# reloadpro.net
KiCad netlist of a schematic drawn in EAGLE
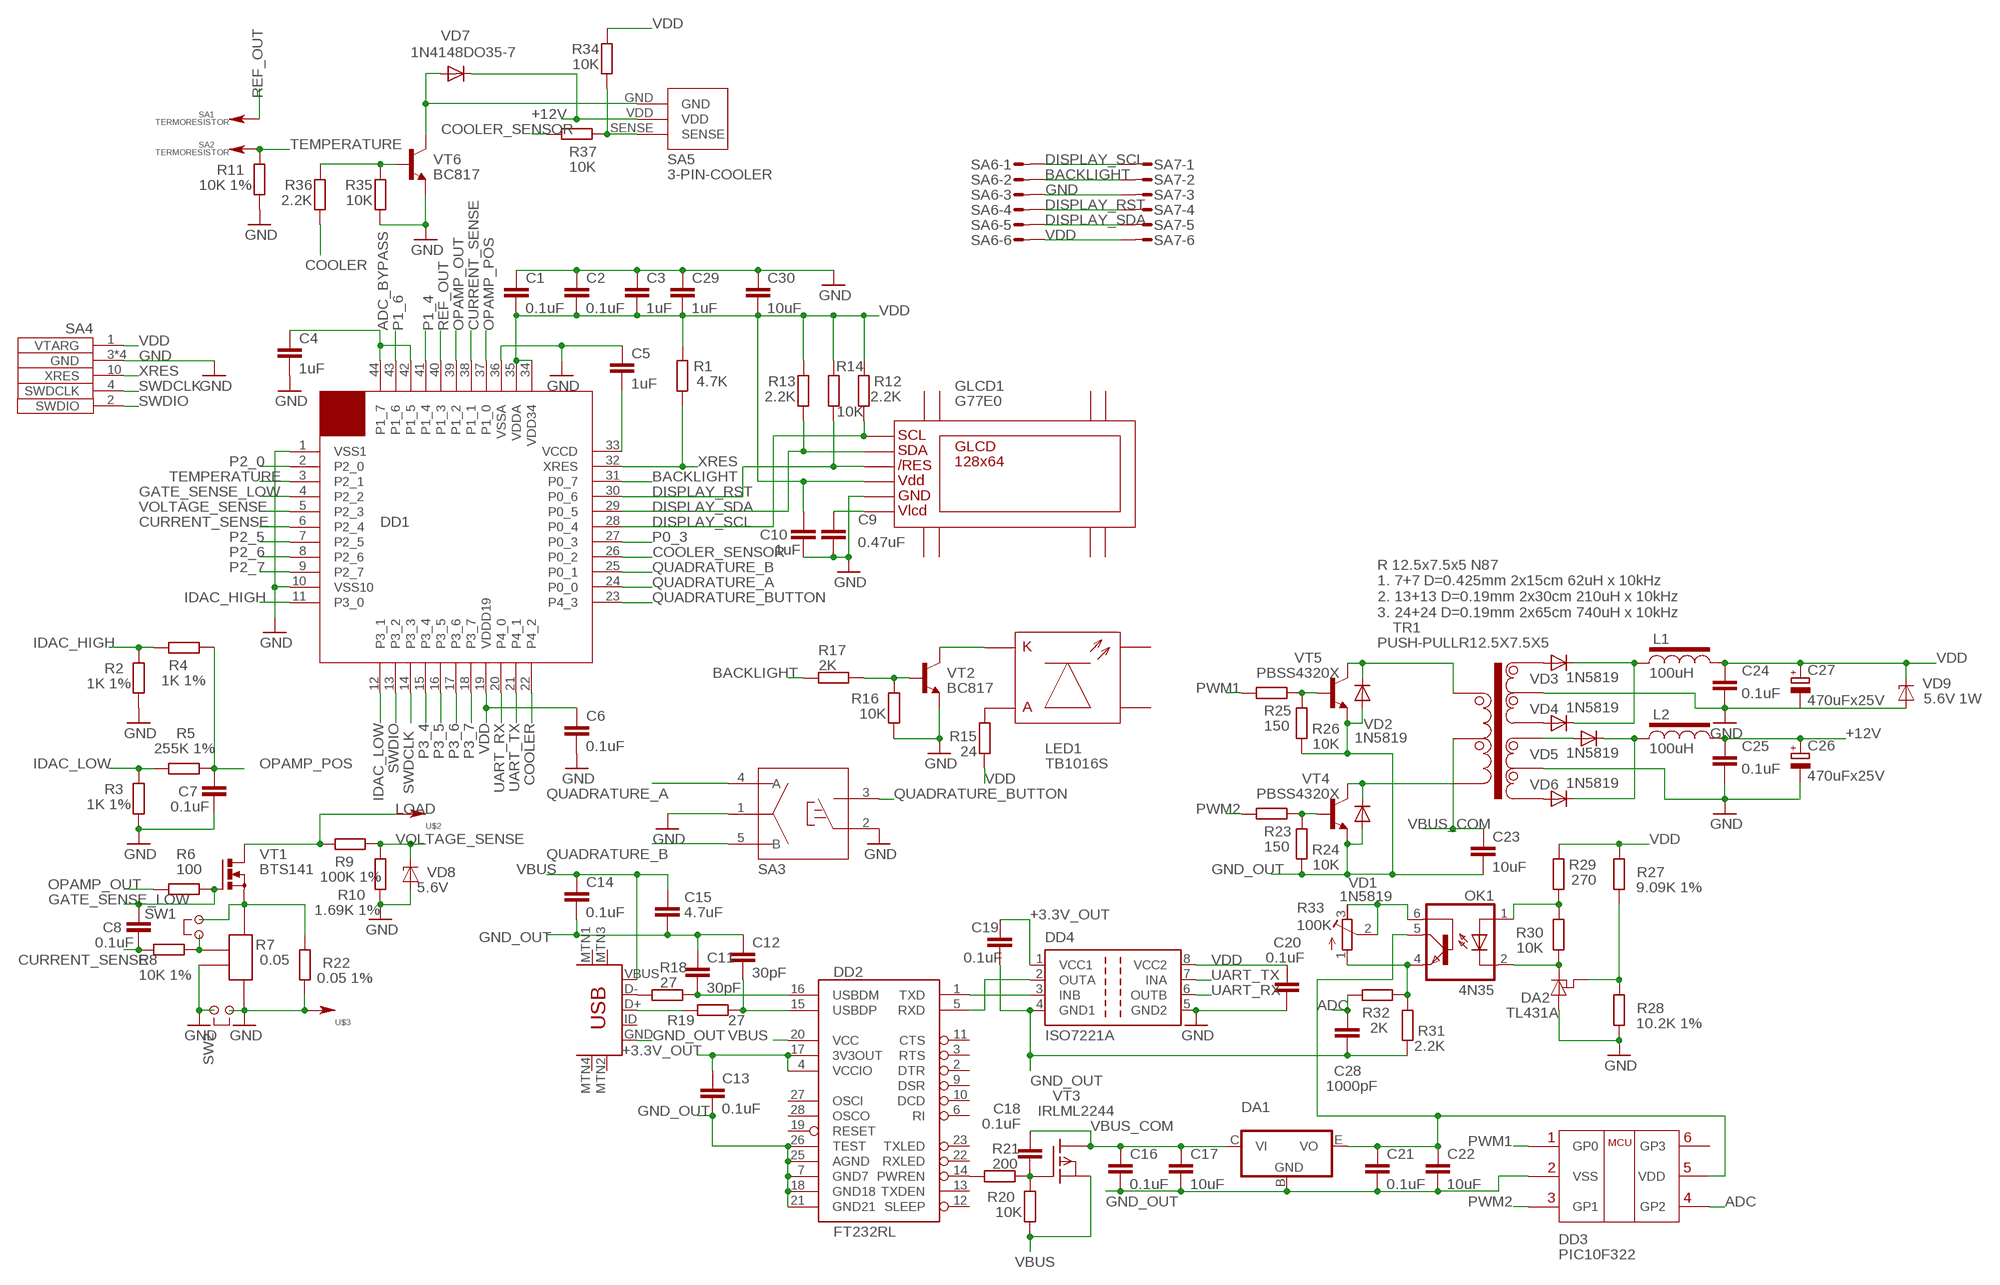
[diagram p0: schematic, sheet 1]

(export (version "E")
  (design (tool "Eeschema 10.0.6"))
  (components
    (comp (ref "C1")
      (value "0.1uF")
      (footprint "eagle-import:C0603")
      (libsource (lib "eagle-import") (part "C-EUC0603"))
    )
    (comp (ref "C2")
      (value "0.1uF")
      (footprint "eagle-import:C0603")
      (libsource (lib "eagle-import") (part "C-EUC0603"))
    )
    (comp (ref "C3")
      (value "1uF")
      (footprint "eagle-import:C0603")
      (libsource (lib "eagle-import") (part "C-EUC0603"))
    )
    (comp (ref "C4")
      (value "1uF")
      (footprint "eagle-import:C0603")
      (libsource (lib "eagle-import") (part "C-EUC0603"))
    )
    (comp (ref "C5")
      (value "1uF")
      (footprint "eagle-import:C0603")
      (libsource (lib "eagle-import") (part "C-EUC0603"))
    )
    (comp (ref "C6")
      (value "0.1uF")
      (footprint "eagle-import:C0603")
      (libsource (lib "eagle-import") (part "C-EUC0603"))
    )
    (comp (ref "C7")
      (value "0.1uF")
      (footprint "eagle-import:C0603")
      (libsource (lib "eagle-import") (part "C-EUC0603"))
    )
    (comp (ref "C8")
      (value "0.1uF")
      (footprint "eagle-import:C0603")
      (libsource (lib "eagle-import") (part "C-EUC0603"))
    )
    (comp (ref "C9")
      (value "0.47uF")
      (footprint "eagle-import:C1206")
      (libsource (lib "eagle-import") (part "C-EUC1206"))
    )
    (comp (ref "C10")
      (value "1uF")
      (footprint "eagle-import:C0603")
      (libsource (lib "eagle-import") (part "C-EUC0603"))
    )
    (comp (ref "C11")
      (value "30pF")
      (footprint "eagle-import:C0603")
      (libsource (lib "eagle-import") (part "C-EUC0603"))
    )
    (comp (ref "C12")
      (value "30pF")
      (footprint "eagle-import:C0603")
      (libsource (lib "eagle-import") (part "C-EUC0603"))
    )
    (comp (ref "C13")
      (value "0.1uF")
      (footprint "eagle-import:C0603")
      (libsource (lib "eagle-import") (part "C-EUC0603"))
    )
    (comp (ref "C14")
      (value "0.1uF")
      (footprint "eagle-import:C0603")
      (libsource (lib "eagle-import") (part "C-EUC0603"))
    )
    (comp (ref "C15")
      (value "4.7uF")
      (footprint "eagle-import:C0805")
      (libsource (lib "eagle-import") (part "C-EUC0805"))
    )
    (comp (ref "C16")
      (value "0.1uF")
      (footprint "eagle-import:C0603")
      (libsource (lib "eagle-import") (part "C-EUC0603"))
    )
    (comp (ref "C17")
      (value "10uF")
      (footprint "eagle-import:C1206")
      (libsource (lib "eagle-import") (part "C-EUC1206"))
    )
    (comp (ref "C18")
      (value "0.1uF")
      (footprint "eagle-import:C0603")
      (libsource (lib "eagle-import") (part "C-EUC0603"))
    )
    (comp (ref "C19")
      (value "0.1uF")
      (footprint "eagle-import:C0603")
      (libsource (lib "eagle-import") (part "C-EUC0603"))
    )
    (comp (ref "C20")
      (value "0.1uF")
      (footprint "eagle-import:C0603")
      (libsource (lib "eagle-import") (part "C-EUC0603"))
    )
    (comp (ref "C21")
      (value "0.1uF")
      (footprint "eagle-import:C0603")
      (libsource (lib "eagle-import") (part "C-EUC0603"))
    )
    (comp (ref "C22")
      (value "10uF")
      (footprint "eagle-import:C1206")
      (libsource (lib "eagle-import") (part "C-EUC1206"))
    )
    (comp (ref "C23")
      (value "10uF")
      (footprint "eagle-import:C1206")
      (libsource (lib "eagle-import") (part "C-EUC1206"))
    )
    (comp (ref "C24")
      (value "0.1uF")
      (footprint "eagle-import:C0603")
      (libsource (lib "eagle-import") (part "C-EUC0603"))
    )
    (comp (ref "C25")
      (value "0.1uF")
      (footprint "eagle-import:C0805")
      (libsource (lib "eagle-import") (part "C-EUC0805"))
    )
    (comp (ref "C26")
      (value "470uFx25V")
      (footprint "eagle-import:E3,5-8")
      (libsource (lib "eagle-import") (part "CPOL-EUE3.5-8"))
    )
    (comp (ref "C27")
      (value "470uFx25V")
      (footprint "eagle-import:E3,5-8")
      (libsource (lib "eagle-import") (part "CPOL-EUE3.5-8"))
    )
    (comp (ref "C28")
      (value "1000pF")
      (footprint "eagle-import:C0805")
      (libsource (lib "eagle-import") (part "C-EUC0805"))
    )
    (comp (ref "C29")
      (value "1uF")
      (footprint "eagle-import:C0603")
      (libsource (lib "eagle-import") (part "C-EUC0603"))
    )
    (comp (ref "C30")
      (value "10uF")
      (footprint "eagle-import:C0805")
      (libsource (lib "eagle-import") (part "C-EUC0805"))
    )
    (comp (ref "DA1")
      (value "78GOR")
      (footprint "eagle-import:TO92-EBC")
      (libsource (lib "eagle-import") (part "78GOR"))
    )
    (comp (ref "DA2")
      (value "TL431A")
      (footprint "eagle-import:TO92-EBC")
      (libsource (lib "eagle-import") (part "TL431TO92"))
    )
    (comp (ref "DD1")
      (value "CY8C4245-AXITQFP44")
      (footprint "eagle-import:TQFP44")
      (libsource (lib "eagle-import") (part "CY8C4245-AXITQFP44"))
    )
    (comp (ref "DD2")
      (value "FT232RL")
      (footprint "eagle-import:SSOP28DB")
      (libsource (lib "eagle-import") (part "FT232RLSSOP"))
    )
    (comp (ref "DD3")
      (value "PIC10F322")
      (footprint "eagle-import:SOT23-6")
      (libsource (lib "eagle-import") (part "PIC10F20XSOT23-6"))
    )
    (comp (ref "DD4")
      (value "ISO7221A")
      (footprint "eagle-import:SO-08")
      (fields (field (name "MPN") "ISO7221AD"))
      (libsource (lib "eagle-import") (part "ISO7221A"))
    )
    (comp (ref "GLCD1")
      (value "G77E0")
      (footprint "eagle-import:G77E0")
      (libsource (lib "eagle-import") (part "G77E0"))
    )
    (comp (ref "L1")
      (value "100uH")
      (footprint "eagle-import:LGA0410")
      (libsource (lib "eagle-import") (part "INDUCTORLGA0410_HOME"))
    )
    (comp (ref "L2")
      (value "100uH")
      (footprint "eagle-import:LGA0410")
      (libsource (lib "eagle-import") (part "INDUCTORLGA0410_HOME"))
    )
    (comp (ref "LED1")
      (value "TB1016S")
      (footprint "eagle-import:TB1016S")
      (libsource (lib "eagle-import") (part "TB1016S"))
    )
    (comp (ref "OK1")
      (value "4N35")
      (footprint "eagle-import:DIL06")
      (fields (field (name "MF") "FAIRCHILD SEMICONDUCTOR"))
      (libsource (lib "eagle-import") (part "4N35"))
    )
    (comp (ref "R1")
      (value "4.7K")
      (footprint "eagle-import:R0603")
      (libsource (lib "eagle-import") (part "R-EU_R0603"))
    )
    (comp (ref "R2")
      (value "1K 1%")
      (footprint "eagle-import:R0603")
      (libsource (lib "eagle-import") (part "R-EU_R0603"))
    )
    (comp (ref "R3")
      (value "1K 1%")
      (footprint "eagle-import:R0603")
      (libsource (lib "eagle-import") (part "R-EU_R0603"))
    )
    (comp (ref "R4")
      (value "1K 1%")
      (footprint "eagle-import:R0603")
      (libsource (lib "eagle-import") (part "R-EU_R0603"))
    )
    (comp (ref "R5")
      (value "255K 1%")
      (footprint "eagle-import:R0805")
      (libsource (lib "eagle-import") (part "R-EU_R0805"))
    )
    (comp (ref "R6")
      (value "100")
      (footprint "eagle-import:R0805")
      (libsource (lib "eagle-import") (part "R-EU_R0805"))
    )
    (comp (ref "R7")
      (value "0.05")
      (footprint "eagle-import:SR10")
      (libsource (lib "eagle-import") (part "SR10SR10"))
    )
    (comp (ref "R8")
      (value "10K 1%")
      (footprint "eagle-import:R0603")
      (libsource (lib "eagle-import") (part "R-EU_R0603"))
    )
    (comp (ref "R9")
      (value "100K 1%")
      (footprint "eagle-import:R0603")
      (libsource (lib "eagle-import") (part "R-EU_R0603"))
    )
    (comp (ref "R10")
      (value "1.69K 1%")
      (footprint "eagle-import:R0805")
      (libsource (lib "eagle-import") (part "R-EU_R0805"))
    )
    (comp (ref "R11")
      (value "10K 1%")
      (footprint "eagle-import:R0603")
      (libsource (lib "eagle-import") (part "R-EU_R0603"))
    )
    (comp (ref "R12")
      (value "2.2K")
      (footprint "eagle-import:R0603")
      (libsource (lib "eagle-import") (part "R-EU_R0603"))
    )
    (comp (ref "R13")
      (value "2.2K")
      (footprint "eagle-import:R0603")
      (libsource (lib "eagle-import") (part "R-EU_R0603"))
    )
    (comp (ref "R14")
      (value "10K")
      (footprint "eagle-import:R0603")
      (libsource (lib "eagle-import") (part "R-EU_R0603"))
    )
    (comp (ref "R15")
      (value "24")
      (footprint "eagle-import:R1206")
      (libsource (lib "eagle-import") (part "R-EU_R1206"))
    )
    (comp (ref "R16")
      (value "10K")
      (footprint "eagle-import:R0603")
      (libsource (lib "eagle-import") (part "R-EU_R0603"))
    )
    (comp (ref "R17")
      (value "2K")
      (footprint "eagle-import:R0603")
      (libsource (lib "eagle-import") (part "R-EU_R0603"))
    )
    (comp (ref "R18")
      (value "27")
      (footprint "eagle-import:R0805")
      (libsource (lib "eagle-import") (part "R-EU_R0805"))
    )
    (comp (ref "R19")
      (value "27")
      (footprint "eagle-import:R0805")
      (libsource (lib "eagle-import") (part "R-EU_R0805"))
    )
    (comp (ref "R20")
      (value "10K")
      (footprint "eagle-import:R0603")
      (libsource (lib "eagle-import") (part "R-EU_R0603"))
    )
    (comp (ref "R21")
      (value "200")
      (footprint "eagle-import:R0603")
      (libsource (lib "eagle-import") (part "R-EU_R0603"))
    )
    (comp (ref "R22")
      (value "0.05 1%")
      (footprint "eagle-import:R2512")
      (libsource (lib "eagle-import") (part "R-EU_R2512"))
    )
    (comp (ref "R23")
      (value "150")
      (footprint "eagle-import:R0805")
      (libsource (lib "eagle-import") (part "R-EU_R0805"))
    )
    (comp (ref "R24")
      (value "10K")
      (footprint "eagle-import:R0603")
      (libsource (lib "eagle-import") (part "R-EU_R0603"))
    )
    (comp (ref "R25")
      (value "150")
      (footprint "eagle-import:R0805")
      (libsource (lib "eagle-import") (part "R-EU_R0805"))
    )
    (comp (ref "R26")
      (value "10K")
      (footprint "eagle-import:R0603")
      (libsource (lib "eagle-import") (part "R-EU_R0603"))
    )
    (comp (ref "R27")
      (value "9.09K 1%")
      (footprint "eagle-import:R0805")
      (libsource (lib "eagle-import") (part "R-EU_R0805"))
    )
    (comp (ref "R28")
      (value "10.2K 1%")
      (footprint "eagle-import:R0805")
      (libsource (lib "eagle-import") (part "R-EU_R0805"))
    )
    (comp (ref "R29")
      (value "270")
      (footprint "eagle-import:R0805")
      (libsource (lib "eagle-import") (part "R-EU_R0805"))
    )
    (comp (ref "R30")
      (value "10K")
      (footprint "eagle-import:R0603")
      (libsource (lib "eagle-import") (part "R-EU_R0603"))
    )
    (comp (ref "R31")
      (value "2.2K")
      (footprint "eagle-import:R0603")
      (libsource (lib "eagle-import") (part "R-EU_R0603"))
    )
    (comp (ref "R32")
      (value "2K")
      (footprint "eagle-import:R0603")
      (libsource (lib "eagle-import") (part "R-EU_R0603"))
    )
    (comp (ref "R33")
      (value "100K")
      (footprint "eagle-import:RTRIM3296H")
      (libsource (lib "eagle-import") (part "R-TRIMM3296H"))
    )
    (comp (ref "R34")
      (value "10K")
      (footprint "eagle-import:R0603")
      (libsource (lib "eagle-import") (part "R-EU_R0603"))
    )
    (comp (ref "R35")
      (value "10K")
      (footprint "eagle-import:R0603")
      (libsource (lib "eagle-import") (part "R-EU_R0603"))
    )
    (comp (ref "R36")
      (value "2.2K")
      (footprint "eagle-import:R0603")
      (libsource (lib "eagle-import") (part "R-EU_R0603"))
    )
    (comp (ref "R37")
      (value "10K")
      (footprint "eagle-import:R0603")
      (libsource (lib "eagle-import") (part "R-EU_R0603"))
    )
    (comp (ref "SA1")
      (value "TERMORESISTOR")
      (footprint "eagle-import:1-PIN_HOME")
      (libsource (lib "eagle-import") (part "1-PINHOME"))
    )
    (comp (ref "SA2")
      (value "TERMORESISTOR")
      (footprint "eagle-import:1-PIN_HOME")
      (libsource (lib "eagle-import") (part "1-PINHOME"))
    )
    (comp (ref "SA3")
      (value "PEC16IDC")
      (footprint "eagle-import:PEC16-IDC")
      (libsource (lib "eagle-import") (part "PEC16IDC"))
    )
    (comp (ref "SA4")
      (value "SWDSMD")
      (footprint "eagle-import:IDC10_1.27SMD")
      (libsource (lib "eagle-import") (part "SWDSMD"))
    )
    (comp (ref "SA5")
      (value "3-PIN-COOLER")
      (footprint "eagle-import:3-PIN-COOLER")
      (libsource (lib "eagle-import") (part "3-PIN-COOLER"))
    )
    (comp (ref "SA6")
      (value "MICROMATCH-6SMD")
      (footprint "eagle-import:MICROMATCH-6SMD")
      (libsource (lib "eagle-import") (part "MICROMATCH-6SMD"))
    )
    (comp (ref "SA7")
      (value "MICROMATCH-6SMD")
      (footprint "eagle-import:MICROMATCH-6SMD")
      (libsource (lib "eagle-import") (part "MICROMATCH-6SMD"))
    )
    (comp (ref "SW1")
      (value "2-PINDIL")
      (footprint "eagle-import:2-PIN")
      (libsource (lib "eagle-import") (part "2-PINDIL"))
    )
    (comp (ref "SW2")
      (value "2-PINDIL")
      (footprint "eagle-import:2-PIN")
      (libsource (lib "eagle-import") (part "2-PINDIL"))
    )
    (comp (ref "TR1")
      (value "PUSH-PULLR12.5X7.5X5")
      (footprint "eagle-import:R12.5X7.5X5PUSHH-PULL")
      (libsource (lib "eagle-import") (part "PUSH-PULLR12.5X7.5X5"))
    )
    (comp (ref "U$1")
      (value "USB-MINIB-5PIN")
      (footprint "eagle-import:USB-MINIB")
      (libsource (lib "eagle-import") (part "USB-MINIB-5PIN"))
    )
    (comp (ref "U$2")
      (value "1-PIN2_54")
      (footprint "eagle-import:1_PIN_2_54")
      (libsource (lib "eagle-import") (part "1-PIN2_54"))
    )
    (comp (ref "U$3")
      (value "1-PIN2_54")
      (footprint "eagle-import:1_PIN_2_54")
      (libsource (lib "eagle-import") (part "1-PIN2_54"))
    )
    (comp (ref "VD1")
      (value "1N5819")
      (footprint "eagle-import:DO41-10")
      (libsource (lib "eagle-import") (part "SM5819DO41-10"))
    )
    (comp (ref "VD2")
      (value "1N5819")
      (footprint "eagle-import:DO41-10")
      (libsource (lib "eagle-import") (part "SM5819DO41-10"))
    )
    (comp (ref "VD3")
      (value "1N5819")
      (footprint "eagle-import:DO41-10")
      (libsource (lib "eagle-import") (part "SM5819DO41-10"))
    )
    (comp (ref "VD4")
      (value "1N5819")
      (footprint "eagle-import:DO41-10")
      (libsource (lib "eagle-import") (part "SM5819DO41-10"))
    )
    (comp (ref "VD5")
      (value "1N5819")
      (footprint "eagle-import:DO41-10")
      (libsource (lib "eagle-import") (part "SM5819DO41-10"))
    )
    (comp (ref "VD6")
      (value "1N5819")
      (footprint "eagle-import:DO41-10")
      (libsource (lib "eagle-import") (part "SM5819DO41-10"))
    )
    (comp (ref "VD7")
      (value "1N4148DO35-7")
      (footprint "eagle-import:DO35-7")
      (libsource (lib "eagle-import") (part "1N4148DO35-7"))
    )
    (comp (ref "VD8")
      (value "5.6V")
      (footprint "eagle-import:STABILITRON")
      (libsource (lib "eagle-import") (part "STABILITRONSMD"))
    )
    (comp (ref "VD9")
      (value "5.6V 1W")
      (footprint "eagle-import:DO35-10")
      (libsource (lib "eagle-import") (part "STABILITRONDO35-10"))
    )
    (comp (ref "VT1")
      (value "BTS141")
      (footprint "eagle-import:TO220BV")
      (libsource (lib "eagle-import") (part "BTS141"))
    )
    (comp (ref "VT2")
      (value "BC817")
      (footprint "eagle-import:SOT23-BEC")
      (libsource (lib "eagle-import") (part "-NPN-SOT23-BECBC817-16LT1"))
    )
    (comp (ref "VT3")
      (value "IRLML2244")
      (footprint "eagle-import:SOT23")
      (libsource (lib "eagle-import") (part "P-MOSFETSOT23"))
    )
    (comp (ref "VT4")
      (value "PBSS4320X")
      (footprint "eagle-import:SOT89-BCE")
      (libsource (lib "eagle-import") (part "-NPN-SOT89-BCE"))
    )
    (comp (ref "VT5")
      (value "PBSS4320X")
      (footprint "eagle-import:SOT89-BCE")
      (libsource (lib "eagle-import") (part "-NPN-SOT89-BCE"))
    )
    (comp (ref "VT6")
      (value "BC817")
      (footprint "eagle-import:SOT23-BEC")
      (libsource (lib "eagle-import") (part "-NPN-SOT23-BECBC817-16LT1"))
    )
  )
  (nets
    (net (code "1") (name "/+3.3V_OUT") (class "Default")
      (node (ref "C13") (pin "1") (pinfunction "1_1") (pintype "passive"))
      (node (ref "C19") (pin "1") (pinfunction "1_1") (pintype "passive"))
      (node (ref "DD2") (pin "17") (pinfunction "3V3OUT_17") (pintype "output"))
      (node (ref "DD2") (pin "4") (pinfunction "VCCIO_4") (pintype "power_in"))
      (node (ref "DD4") (pin "1") (pinfunction "VCC1_1") (pintype "power_in"))
    )
    (net (code "2") (name "/+12V") (class "Default")
      (node (ref "C25") (pin "1") (pinfunction "1_1") (pintype "passive"))
      (node (ref "C26") (pin "+") (pinfunction "+_+") (pintype "passive"))
      (node (ref "L2") (pin "P$2") (pinfunction "L2_P$2") (pintype "passive"))
      (node (ref "SA5") (pin "VDD") (pinfunction "VDD_VDD") (pintype "power_in"))
      (node (ref "VD7") (pin "C") (pinfunction "C_C") (pintype "passive"))
    )
    (net (code "3") (name "/ADC") (class "Default")
      (node (ref "C28") (pin "1") (pinfunction "1_1") (pintype "passive"))
      (node (ref "DD3") (pin "4") (pinfunction "GP2_4") (pintype "bidirectional"))
      (node (ref "R32") (pin "1") (pinfunction "1_1") (pintype "passive"))
    )
    (net (code "4") (name "/ADC_BYPASS") (class "Default")
      (node (ref "C4") (pin "1") (pinfunction "1_1") (pintype "passive"))
      (node (ref "DD1") (pin "42") (pinfunction "P1_5_42") (pintype "bidirectional"))
      (node (ref "DD1") (pin "44") (pinfunction "P1_7_44") (pintype "bidirectional"))
    )
    (net (code "5") (name "/BACKLIGHT") (class "Default")
      (node (ref "DD1") (pin "31") (pinfunction "P0_7_31") (pintype "bidirectional"))
      (node (ref "R17") (pin "2") (pinfunction "2_2") (pintype "passive"))
      (node (ref "SA6") (pin "2") (pinfunction "S_2") (pintype "passive"))
      (node (ref "SA7") (pin "2") (pinfunction "S_2") (pintype "passive"))
    )
    (net (code "6") (name "/COOLER") (class "Default")
      (node (ref "DD1") (pin "22") (pinfunction "P4_2_22") (pintype "bidirectional"))
      (node (ref "R36") (pin "1") (pinfunction "1_1") (pintype "passive"))
    )
    (net (code "7") (name "/COOLER_SENSOR") (class "Default")
      (node (ref "DD1") (pin "26") (pinfunction "P0_2_26") (pintype "bidirectional"))
      (node (ref "R37") (pin "2") (pinfunction "2_2") (pintype "passive"))
    )
    (net (code "8") (name "/CURRENT_SENSE") (class "Default")
      (node (ref "C8") (pin "2") (pinfunction "2_2") (pintype "passive"))
      (node (ref "DD1") (pin "38") (pinfunction "P1_1_38") (pintype "bidirectional"))
      (node (ref "DD1") (pin "6") (pinfunction "P2_4_6") (pintype "bidirectional"))
      (node (ref "R8") (pin "2") (pinfunction "2_2") (pintype "passive"))
    )
    (net (code "9") (name "/DISPLAY_RST") (class "Default")
      (node (ref "DD1") (pin "30") (pinfunction "P0_6_30") (pintype "bidirectional"))
      (node (ref "GLCD1") (pin "/RES") (pinfunction "/RES_/RES") (pintype "input"))
      (node (ref "R14") (pin "1") (pinfunction "1_1") (pintype "passive"))
      (node (ref "SA6") (pin "4") (pinfunction "S_4") (pintype "passive"))
      (node (ref "SA7") (pin "4") (pinfunction "S_4") (pintype "passive"))
    )
    (net (code "10") (name "/DISPLAY_SCL") (class "Default")
      (node (ref "DD1") (pin "28") (pinfunction "P0_4_28") (pintype "bidirectional"))
      (node (ref "GLCD1") (pin "SCL") (pinfunction "SCL_SCL") (pintype "input"))
      (node (ref "R12") (pin "1") (pinfunction "1_1") (pintype "passive"))
      (node (ref "SA6") (pin "1") (pinfunction "S_1") (pintype "passive"))
      (node (ref "SA7") (pin "1") (pinfunction "S_1") (pintype "passive"))
    )
    (net (code "11") (name "/DISPLAY_SDA") (class "Default")
      (node (ref "DD1") (pin "29") (pinfunction "P0_5_29") (pintype "bidirectional"))
      (node (ref "GLCD1") (pin "SDA") (pinfunction "SDA_SDA") (pintype "bidirectional"))
      (node (ref "R13") (pin "1") (pinfunction "1_1") (pintype "passive"))
      (node (ref "SA6") (pin "5") (pinfunction "S_5") (pintype "passive"))
      (node (ref "SA7") (pin "5") (pinfunction "S_5") (pintype "passive"))
    )
    (net (code "12") (name "/GATE_SENSE_LOW") (class "Default")
      (node (ref "C8") (pin "1") (pinfunction "1_1") (pintype "passive"))
      (node (ref "DD1") (pin "4") (pinfunction "P2_2_4") (pintype "bidirectional"))
      (node (ref "R6") (pin "1") (pinfunction "1_1") (pintype "passive"))
      (node (ref "VT1") (pin "G") (pinfunction "G_G") (pintype "passive"))
    )
    (net (code "13") (name "/GND_OUT") (class "Default")
      (node (ref "C11") (pin "1") (pinfunction "1_1") (pintype "passive"))
      (node (ref "C12") (pin "1") (pinfunction "1_1") (pintype "passive"))
      (node (ref "C13") (pin "2") (pinfunction "2_2") (pintype "passive"))
      (node (ref "C14") (pin "2") (pinfunction "2_2") (pintype "passive"))
      (node (ref "C15") (pin "2") (pinfunction "2_2") (pintype "passive"))
      (node (ref "C16") (pin "2") (pinfunction "2_2") (pintype "passive"))
      (node (ref "C17") (pin "2") (pinfunction "2_2") (pintype "passive"))
      (node (ref "C19") (pin "2") (pinfunction "2_2") (pintype "passive"))
      (node (ref "C21") (pin "2") (pinfunction "2_2") (pintype "passive"))
      (node (ref "C22") (pin "2") (pinfunction "2_2") (pintype "passive"))
      (node (ref "C23") (pin "2") (pinfunction "2_2") (pintype "passive"))
      (node (ref "C28") (pin "2") (pinfunction "2_2") (pintype "passive"))
      (node (ref "DA1") (pin "B") (pinfunction "GND_B") (pintype "passive"))
      (node (ref "DD2") (pin "18") (pinfunction "GND18_18") (pintype "power_in"))
      (node (ref "DD2") (pin "21") (pinfunction "GND21_21") (pintype "power_in"))
      (node (ref "DD2") (pin "25") (pinfunction "AGND_25") (pintype "power_in"))
      (node (ref "DD2") (pin "26") (pinfunction "TEST_26") (pintype "input"))
      (node (ref "DD2") (pin "7") (pinfunction "GND7_7") (pintype "power_in"))
      (node (ref "DD3") (pin "2") (pinfunction "VSS_2") (pintype "power_in"))
      (node (ref "DD4") (pin "4") (pinfunction "GND1_4") (pintype "power_in"))
      (node (ref "R24") (pin "1") (pinfunction "1_1") (pintype "passive"))
      (node (ref "R26") (pin "1") (pinfunction "1_1") (pintype "passive"))
      (node (ref "R31") (pin "2") (pinfunction "2_2") (pintype "passive"))
      (node (ref "U$1") (pin "GND") (pinfunction "GND_GND") (pintype "bidirectional"))
      (node (ref "VD1") (pin "A") (pinfunction "A_A") (pintype "passive"))
      (node (ref "VD2") (pin "A") (pinfunction "A_A") (pintype "passive"))
      (node (ref "VT4") (pin "E") (pinfunction "E_E") (pintype "passive"))
      (node (ref "VT5") (pin "E") (pinfunction "E_E") (pintype "passive"))
    )
    (net (code "14") (name "/IDAC_HIGH") (class "Default")
      (node (ref "DD1") (pin "11") (pinfunction "P3_0_11") (pintype "bidirectional"))
      (node (ref "R2") (pin "2") (pinfunction "2_2") (pintype "passive"))
      (node (ref "R4") (pin "2") (pinfunction "2_2") (pintype "passive"))
    )
    (net (code "15") (name "/IDAC_LOW") (class "Default")
      (node (ref "DD1") (pin "12") (pinfunction "P3_1_12") (pintype "bidirectional"))
      (node (ref "R3") (pin "2") (pinfunction "2_2") (pintype "passive"))
      (node (ref "R5") (pin "2") (pinfunction "2_2") (pintype "passive"))
    )
    (net (code "16") (name "/LOAD") (class "Default")
      (node (ref "R9") (pin "2") (pinfunction "2_2") (pintype "passive"))
      (node (ref "U$2") (pin "P$1") (pinfunction "S_P$1") (pintype "passive"))
      (node (ref "VT1") (pin "D") (pinfunction "D_D") (pintype "passive"))
    )
    (net (code "17") (name "/OPAMP_OUT") (class "Default")
      (node (ref "DD1") (pin "39") (pinfunction "P1_2_39") (pintype "bidirectional"))
      (node (ref "R6") (pin "2") (pinfunction "2_2") (pintype "passive"))
    )
    (net (code "18") (name "/OPAMP_POS") (class "Default")
      (node (ref "C7") (pin "1") (pinfunction "1_1") (pintype "passive"))
      (node (ref "DD1") (pin "37") (pinfunction "P1_0_37") (pintype "bidirectional"))
      (node (ref "R4") (pin "1") (pinfunction "1_1") (pintype "passive"))
      (node (ref "R5") (pin "1") (pinfunction "1_1") (pintype "passive"))
    )
    (net (code "19") (name "/P0_3") (class "Default")
      (node (ref "DD1") (pin "27") (pinfunction "P0_3_27") (pintype "bidirectional"))
    )
    (net (code "20") (name "/P1_4") (class "Default")
      (node (ref "DD1") (pin "41") (pinfunction "P1_4_41") (pintype "bidirectional"))
    )
    (net (code "21") (name "/P1_6") (class "Default")
      (node (ref "DD1") (pin "43") (pinfunction "P1_6_43") (pintype "bidirectional"))
    )
    (net (code "22") (name "/P2_0") (class "Default")
      (node (ref "DD1") (pin "2") (pinfunction "P2_0_2") (pintype "bidirectional"))
    )
    (net (code "23") (name "/P2_5") (class "Default")
      (node (ref "DD1") (pin "7") (pinfunction "P2_5_7") (pintype "bidirectional"))
    )
    (net (code "24") (name "/P2_6") (class "Default")
      (node (ref "DD1") (pin "8") (pinfunction "P2_6_8") (pintype "bidirectional"))
    )
    (net (code "25") (name "/P2_7") (class "Default")
      (node (ref "DD1") (pin "9") (pinfunction "P2_7_9") (pintype "bidirectional"))
    )
    (net (code "26") (name "/P3_4") (class "Default")
      (node (ref "DD1") (pin "15") (pinfunction "P3_4_15") (pintype "bidirectional"))
    )
    (net (code "27") (name "/P3_5") (class "Default")
      (node (ref "DD1") (pin "16") (pinfunction "P3_5_16") (pintype "bidirectional"))
    )
    (net (code "28") (name "/P3_6") (class "Default")
      (node (ref "DD1") (pin "17") (pinfunction "P3_6_17") (pintype "bidirectional"))
    )
    (net (code "29") (name "/P3_7") (class "Default")
      (node (ref "DD1") (pin "18") (pinfunction "P3_7_18") (pintype "bidirectional"))
    )
    (net (code "30") (name "/PWM1") (class "Default")
      (node (ref "DD3") (pin "1") (pinfunction "GP0_1") (pintype "bidirectional"))
      (node (ref "R25") (pin "1") (pinfunction "1_1") (pintype "passive"))
    )
    (net (code "31") (name "/PWM2") (class "Default")
      (node (ref "DD3") (pin "3") (pinfunction "GP1_3") (pintype "bidirectional"))
      (node (ref "R23") (pin "1") (pinfunction "1_1") (pintype "passive"))
    )
    (net (code "32") (name "/QUADRATURE_A") (class "Default")
      (node (ref "DD1") (pin "24") (pinfunction "P0_0_24") (pintype "bidirectional"))
      (node (ref "SA3") (pin "4") (pinfunction "A_4") (pintype "passive"))
    )
    (net (code "33") (name "/QUADRATURE_B") (class "Default")
      (node (ref "DD1") (pin "25") (pinfunction "P0_1_25") (pintype "bidirectional"))
      (node (ref "SA3") (pin "5") (pinfunction "B_5") (pintype "passive"))
    )
    (net (code "34") (name "/QUADRATURE_BUTTON") (class "Default")
      (node (ref "DD1") (pin "23") (pinfunction "P4_3_23") (pintype "bidirectional"))
      (node (ref "SA3") (pin "3") (pinfunction "B1_3") (pintype "passive"))
    )
    (net (code "35") (name "/REF_OUT") (class "Default")
      (node (ref "DD1") (pin "40") (pinfunction "P1_3_40") (pintype "bidirectional"))
      (node (ref "SA1") (pin "P$1") (pinfunction "S_P$1") (pintype "passive"))
    )
    (net (code "36") (name "/SWDCLK") (class "Default")
      (node (ref "DD1") (pin "14") (pinfunction "P3_3_14") (pintype "bidirectional"))
      (node (ref "SA4") (pin "4") (pinfunction "SWDCLK_4") (pintype "bidirectional"))
    )
    (net (code "37") (name "/SWDIO") (class "Default")
      (node (ref "DD1") (pin "13") (pinfunction "P3_2_13") (pintype "bidirectional"))
      (node (ref "SA4") (pin "2") (pinfunction "SWDIO_2") (pintype "bidirectional"))
    )
    (net (code "38") (name "/TEMPERATURE") (class "Default")
      (node (ref "DD1") (pin "3") (pinfunction "P2_1_3") (pintype "bidirectional"))
      (node (ref "R11") (pin "2") (pinfunction "2_2") (pintype "passive"))
      (node (ref "SA2") (pin "P$1") (pinfunction "S_P$1") (pintype "passive"))
    )
    (net (code "39") (name "/UART_RX") (class "Default")
      (node (ref "DD1") (pin "20") (pinfunction "P4_0_20") (pintype "bidirectional"))
      (node (ref "DD4") (pin "6") (pinfunction "OUTB_6") (pintype "output"))
    )
    (net (code "40") (name "/UART_TX") (class "Default")
      (node (ref "DD1") (pin "21") (pinfunction "P4_1_21") (pintype "bidirectional"))
      (node (ref "DD4") (pin "7") (pinfunction "INA_7") (pintype "input"))
    )
    (net (code "41") (name "/VBUS") (class "Default")
      (node (ref "C14") (pin "1") (pinfunction "1_1") (pintype "passive"))
      (node (ref "C15") (pin "1") (pinfunction "1_1") (pintype "passive"))
      (node (ref "DD2") (pin "20") (pinfunction "VCC_20") (pintype "power_in"))
      (node (ref "R20") (pin "1") (pinfunction "1_1") (pintype "passive"))
      (node (ref "U$1") (pin "VBUS") (pinfunction "VBUS_VBUS") (pintype "bidirectional"))
      (node (ref "VT3") (pin "2") (pinfunction "S_2") (pintype "passive"))
    )
    (net (code "42") (name "/VBUS_COM") (class "Default")
      (node (ref "C16") (pin "1") (pinfunction "1_1") (pintype "passive"))
      (node (ref "C17") (pin "1") (pinfunction "1_1") (pintype "passive"))
      (node (ref "C18") (pin "2") (pinfunction "2_2") (pintype "passive"))
      (node (ref "C23") (pin "1") (pinfunction "1_1") (pintype "passive"))
      (node (ref "DA1") (pin "C") (pinfunction "VI_C") (pintype "input"))
      (node (ref "TR1") (pin "W1-COM") (pinfunction "W1-COM_W1-COM") (pintype "bidirectional"))
      (node (ref "TR1") (pin "W1-COM1") (pinfunction "W1-COM_W1-COM1") (pintype "bidirectional"))
      (node (ref "VT3") (pin "3") (pinfunction "D_3") (pintype "passive"))
    )
    (net (code "43") (name "/VDD") (class "Default")
      (node (ref "C1") (pin "2") (pinfunction "2_2") (pintype "passive"))
      (node (ref "C10") (pin "1") (pinfunction "1_1") (pintype "passive"))
      (node (ref "C2") (pin "2") (pinfunction "2_2") (pintype "passive"))
      (node (ref "C20") (pin "1") (pinfunction "1_1") (pintype "passive"))
      (node (ref "C24") (pin "1") (pinfunction "1_1") (pintype "passive"))
      (node (ref "C27") (pin "+") (pinfunction "+_+") (pintype "passive"))
      (node (ref "C29") (pin "2") (pinfunction "2_2") (pintype "passive"))
      (node (ref "C3") (pin "2") (pinfunction "2_2") (pintype "passive"))
      (node (ref "C30") (pin "2") (pinfunction "2_2") (pintype "passive"))
      (node (ref "C6") (pin "1") (pinfunction "1_1") (pintype "passive"))
      (node (ref "DD1") (pin "19") (pinfunction "VDDD19_19") (pintype "power_in"))
      (node (ref "DD1") (pin "34") (pinfunction "VDD34_34") (pintype "power_in"))
      (node (ref "DD1") (pin "35") (pinfunction "VDDA_35") (pintype "power_in"))
      (node (ref "DD4") (pin "8") (pinfunction "VCC2_8") (pintype "power_in"))
      (node (ref "GLCD1") (pin "VDD") (pinfunction "VDD_VDD") (pintype "power_in"))
      (node (ref "L1") (pin "P$2") (pinfunction "L2_P$2") (pintype "passive"))
      (node (ref "R1") (pin "2") (pinfunction "2_2") (pintype "passive"))
      (node (ref "R12") (pin "2") (pinfunction "2_2") (pintype "passive"))
      (node (ref "R13") (pin "2") (pinfunction "2_2") (pintype "passive"))
      (node (ref "R14") (pin "2") (pinfunction "2_2") (pintype "passive"))
      (node (ref "R15") (pin "2") (pinfunction "2_2") (pintype "passive"))
      (node (ref "R27") (pin "1") (pinfunction "1_1") (pintype "passive"))
      (node (ref "R29") (pin "1") (pinfunction "1_1") (pintype "passive"))
      (node (ref "R34") (pin "2") (pinfunction "2_2") (pintype "passive"))
      (node (ref "SA4") (pin "1") (pinfunction "VTARG_1") (pintype "bidirectional"))
      (node (ref "SA6") (pin "6") (pinfunction "S_6") (pintype "passive"))
      (node (ref "SA7") (pin "6") (pinfunction "S_6") (pintype "passive"))
      (node (ref "VD9") (pin "C") (pinfunction "C_C") (pintype "passive"))
    )
    (net (code "44") (name "/VOLTAGE_SENSE") (class "Default")
      (node (ref "DD1") (pin "5") (pinfunction "P2_3_5") (pintype "bidirectional"))
      (node (ref "R10") (pin "1") (pinfunction "1_1") (pintype "passive"))
      (node (ref "R9") (pin "1") (pinfunction "1_1") (pintype "passive"))
      (node (ref "VD8") (pin "C") (pinfunction "C_C") (pintype "passive"))
    )
    (net (code "45") (name "/XRES") (class "Default")
      (node (ref "DD1") (pin "32") (pinfunction "XRES_32") (pintype "input"))
      (node (ref "R1") (pin "1") (pinfunction "1_1") (pintype "passive"))
      (node (ref "SA4") (pin "10") (pinfunction "XRES_10") (pintype "bidirectional"))
    )
    (net (code "46") (name "GND") (class "Default")
      (node (ref "C1") (pin "1") (pinfunction "1_1") (pintype "passive"))
      (node (ref "C10") (pin "2") (pinfunction "2_2") (pintype "passive"))
      (node (ref "C2") (pin "1") (pinfunction "1_1") (pintype "passive"))
      (node (ref "C20") (pin "2") (pinfunction "2_2") (pintype "passive"))
      (node (ref "C24") (pin "2") (pinfunction "2_2") (pintype "passive"))
      (node (ref "C25") (pin "2") (pinfunction "2_2") (pintype "passive"))
      (node (ref "C26") (pin "-") (pinfunction "-_-") (pintype "passive"))
      (node (ref "C27") (pin "-") (pinfunction "-_-") (pintype "passive"))
      (node (ref "C29") (pin "1") (pinfunction "1_1") (pintype "passive"))
      (node (ref "C3") (pin "1") (pinfunction "1_1") (pintype "passive"))
      (node (ref "C30") (pin "1") (pinfunction "1_1") (pintype "passive"))
      (node (ref "C4") (pin "2") (pinfunction "2_2") (pintype "passive"))
      (node (ref "C5") (pin "1") (pinfunction "1_1") (pintype "passive"))
      (node (ref "C6") (pin "2") (pinfunction "2_2") (pintype "passive"))
      (node (ref "C7") (pin "2") (pinfunction "2_2") (pintype "passive"))
      (node (ref "C9") (pin "2") (pinfunction "2_2") (pintype "passive"))
      (node (ref "DA2") (pin "B") (pinfunction "A_B") (pintype "passive"))
      (node (ref "DD1") (pin "1") (pinfunction "VSS1_1") (pintype "power_in"))
      (node (ref "DD1") (pin "10") (pinfunction "VSS10_10") (pintype "power_in"))
      (node (ref "DD1") (pin "36") (pinfunction "VSSA_36") (pintype "power_in"))
      (node (ref "DD4") (pin "5") (pinfunction "GND2_5") (pintype "power_in"))
      (node (ref "GLCD1") (pin "GND") (pinfunction "GND_GND") (pintype "power_in"))
      (node (ref "R10") (pin "2") (pinfunction "2_2") (pintype "passive"))
      (node (ref "R11") (pin "1") (pinfunction "1_1") (pintype "passive"))
      (node (ref "R16") (pin "1") (pinfunction "1_1") (pintype "passive"))
      (node (ref "R2") (pin "1") (pinfunction "1_1") (pintype "passive"))
      (node (ref "R22") (pin "2") (pinfunction "2_2") (pintype "passive"))
      (node (ref "R28") (pin "2") (pinfunction "2_2") (pintype "passive"))
      (node (ref "R3") (pin "1") (pinfunction "1_1") (pintype "passive"))
      (node (ref "R35") (pin "1") (pinfunction "1_1") (pintype "passive"))
      (node (ref "R7") (pin "1") (pinfunction "1_1") (pintype "passive"))
      (node (ref "R7") (pin "2") (pinfunction "2_2") (pintype "passive"))
      (node (ref "SA3") (pin "1") (pinfunction "C_1") (pintype "passive"))
      (node (ref "SA3") (pin "2") (pinfunction "B2_2") (pintype "passive"))
      (node (ref "SA4") (pin "3") (pinfunction "GND_3") (pintype "bidirectional"))
      (node (ref "SA4") (pin "5") (pinfunction "GND_5") (pintype "bidirectional"))
      (node (ref "SA4") (pin "7") (pinfunction "GND_7") (pintype "bidirectional"))
      (node (ref "SA4") (pin "9") (pinfunction "GND_9") (pintype "bidirectional"))
      (node (ref "SA6") (pin "3") (pinfunction "S_3") (pintype "passive"))
      (node (ref "SA7") (pin "3") (pinfunction "S_3") (pintype "passive"))
      (node (ref "SW2") (pin "1") (pinfunction "1_1") (pintype "passive"))
      (node (ref "SW2") (pin "2") (pinfunction "2_2") (pintype "passive"))
      (node (ref "TR1") (pin "W2-COM") (pinfunction "W2-COM_W2-COM") (pintype "bidirectional"))
      (node (ref "TR1") (pin "W2-COM1") (pinfunction "W2-COM_W2-COM1") (pintype "bidirectional"))
      (node (ref "TR1") (pin "W3-COM") (pinfunction "W3-COM_W3-COM") (pintype "bidirectional"))
      (node (ref "TR1") (pin "W3-COM1") (pinfunction "W3-COM_W3-COM1") (pintype "bidirectional"))
      (node (ref "U$3") (pin "P$1") (pinfunction "S_P$1") (pintype "passive"))
      (node (ref "VD8") (pin "A") (pinfunction "A_A") (pintype "passive"))
      (node (ref "VD9") (pin "A") (pinfunction "A_A") (pintype "passive"))
      (node (ref "VT2") (pin "E") (pinfunction "E_E") (pintype "passive"))
      (node (ref "VT6") (pin "E") (pinfunction "E_E") (pintype "passive"))
    )
    (net (code "47") (name "Net-(C9-Pad1)") (class "Default")
      (node (ref "C9") (pin "1") (pinfunction "1_1") (pintype "passive"))
      (node (ref "GLCD1") (pin "VLCD") (pinfunction "VLCD_VLCD") (pintype "power_in"))
    )
    (net (code "48") (name "Net-(DA1-VO)") (class "Default")
      (node (ref "C21") (pin "1") (pinfunction "1_1") (pintype "passive"))
      (node (ref "C22") (pin "1") (pinfunction "1_1") (pintype "passive"))
      (node (ref "DA1") (pin "E") (pinfunction "VO_E") (pintype "passive"))
      (node (ref "DD3") (pin "5") (pinfunction "VDD_5") (pintype "power_in"))
      (node (ref "OK1") (pin "5") (pinfunction "COL_5") (pintype "passive"))
    )
    (net (code "49") (name "Net-(DA2-REF)") (class "Default")
      (node (ref "DA2") (pin "E") (pinfunction "REF_E") (pintype "passive"))
      (node (ref "R27") (pin "2") (pinfunction "2_2") (pintype "passive"))
      (node (ref "R28") (pin "1") (pinfunction "1_1") (pintype "passive"))
    )
    (net (code "50") (name "Net-(DD1-VCCD)") (class "Default")
      (node (ref "C5") (pin "2") (pinfunction "2_2") (pintype "passive"))
      (node (ref "DD1") (pin "33") (pinfunction "VCCD_33") (pintype "power_in"))
    )
    (net (code "51") (name "Net-(DD2-PWREN)") (class "Default")
      (node (ref "DD2") (pin "14") (pinfunction "PWREN_14") (pintype "input"))
      (node (ref "R21") (pin "2") (pinfunction "2_2") (pintype "passive"))
    )
    (net (code "52") (name "Net-(DD2-RXD)") (class "Default")
      (node (ref "DD2") (pin "5") (pinfunction "RXD_5") (pintype "input"))
      (node (ref "DD4") (pin "2") (pinfunction "OUTA_2") (pintype "output"))
    )
    (net (code "53") (name "Net-(DD2-TXD)") (class "Default")
      (node (ref "DD2") (pin "1") (pinfunction "TXD_1") (pintype "output"))
      (node (ref "DD4") (pin "3") (pinfunction "INB_3") (pintype "input"))
    )
    (net (code "54") (name "Net-(DD2-USBDM)") (class "Default")
      (node (ref "C11") (pin "2") (pinfunction "2_2") (pintype "passive"))
      (node (ref "DD2") (pin "16") (pinfunction "USBDM_16") (pintype "bidirectional"))
      (node (ref "R18") (pin "2") (pinfunction "2_2") (pintype "passive"))
    )
    (net (code "55") (name "Net-(DD2-USBDP)") (class "Default")
      (node (ref "C12") (pin "2") (pinfunction "2_2") (pintype "passive"))
      (node (ref "DD2") (pin "15") (pinfunction "USBDP_15") (pintype "bidirectional"))
      (node (ref "R19") (pin "2") (pinfunction "2_2") (pintype "passive"))
    )
    (net (code "56") (name "Net-(L1-L1)") (class "Default")
      (node (ref "L1") (pin "P$1") (pinfunction "L1_P$1") (pintype "passive"))
      (node (ref "VD3") (pin "C") (pinfunction "C_C") (pintype "passive"))
      (node (ref "VD4") (pin "C") (pinfunction "C_C") (pintype "passive"))
    )
    (net (code "57") (name "Net-(L2-L1)") (class "Default")
      (node (ref "L2") (pin "P$1") (pinfunction "L1_P$1") (pintype "passive"))
      (node (ref "VD5") (pin "C") (pinfunction "C_C") (pintype "passive"))
      (node (ref "VD6") (pin "C") (pinfunction "C_C") (pintype "passive"))
    )
    (net (code "58") (name "Net-(LED1-PadA)") (class "Default")
      (node (ref "LED1") (pin "A") (pinfunction "A_A") (pintype "passive"))
      (node (ref "R15") (pin "1") (pinfunction "1_1") (pintype "passive"))
    )
    (net (code "59") (name "Net-(LED1-PadK)") (class "Default")
      (node (ref "LED1") (pin "K") (pinfunction "K_K") (pintype "passive"))
      (node (ref "VT2") (pin "C") (pinfunction "C_C") (pintype "passive"))
    )
    (net (code "60") (name "Net-(OK1-A)") (class "Default")
      (node (ref "OK1") (pin "1") (pinfunction "A_1") (pintype "passive"))
      (node (ref "R29") (pin "2") (pinfunction "2_2") (pintype "passive"))
      (node (ref "R30") (pin "1") (pinfunction "1_1") (pintype "passive"))
    )
    (net (code "61") (name "Net-(OK1-BAS)") (class "Default")
      (node (ref "OK1") (pin "6") (pinfunction "BAS_6") (pintype "passive"))
      (node (ref "R33") (pin "2") (pinfunction "S_2") (pintype "passive"))
      (node (ref "R33") (pin "3") (pinfunction "A_3") (pintype "passive"))
    )
    (net (code "62") (name "Net-(OK1-C)") (class "Default")
      (node (ref "DA2") (pin "C") (pinfunction "C_C") (pintype "passive"))
      (node (ref "OK1") (pin "2") (pinfunction "C_2") (pintype "passive"))
      (node (ref "R30") (pin "2") (pinfunction "2_2") (pintype "passive"))
    )
    (net (code "63") (name "Net-(OK1-EMI)") (class "Default")
      (node (ref "OK1") (pin "4") (pinfunction "EMI_4") (pintype "passive"))
      (node (ref "R31") (pin "1") (pinfunction "1_1") (pintype "passive"))
      (node (ref "R32") (pin "2") (pinfunction "2_2") (pintype "passive"))
      (node (ref "R33") (pin "1") (pinfunction "E_1") (pintype "passive"))
    )
    (net (code "64") (name "Net-(R7-Pad3)") (class "Default")
      (node (ref "R7") (pin "3") (pinfunction "3_3") (pintype "passive"))
      (node (ref "R8") (pin "1") (pinfunction "1_1") (pintype "passive"))
      (node (ref "SW1") (pin "1") (pinfunction "1_1") (pintype "passive"))
    )
    (net (code "65") (name "Net-(R16-Pad2)") (class "Default")
      (node (ref "R16") (pin "2") (pinfunction "2_2") (pintype "passive"))
      (node (ref "R17") (pin "1") (pinfunction "1_1") (pintype "passive"))
      (node (ref "VT2") (pin "B") (pinfunction "B_B") (pintype "passive"))
    )
    (net (code "66") (name "Net-(R18-Pad1)") (class "Default")
      (node (ref "R18") (pin "1") (pinfunction "1_1") (pintype "passive"))
      (node (ref "U$1") (pin "D-") (pinfunction "D-_D-") (pintype "bidirectional"))
    )
    (net (code "67") (name "Net-(R19-Pad1)") (class "Default")
      (node (ref "R19") (pin "1") (pinfunction "1_1") (pintype "passive"))
      (node (ref "U$1") (pin "D+") (pinfunction "D+_D+") (pintype "bidirectional"))
    )
    (net (code "68") (name "Net-(R22-Pad1)") (class "Default")
      (node (ref "R22") (pin "1") (pinfunction "1_1") (pintype "passive"))
      (node (ref "R7") (pin "4") (pinfunction "4_4") (pintype "passive"))
      (node (ref "SW1") (pin "2") (pinfunction "2_2") (pintype "passive"))
      (node (ref "VT1") (pin "S") (pinfunction "S_S") (pintype "passive"))
    )
    (net (code "69") (name "Net-(R23-Pad2)") (class "Default")
      (node (ref "R23") (pin "2") (pinfunction "2_2") (pintype "passive"))
      (node (ref "R24") (pin "2") (pinfunction "2_2") (pintype "passive"))
      (node (ref "VT4") (pin "B") (pinfunction "B_B") (pintype "passive"))
    )
    (net (code "70") (name "Net-(R25-Pad2)") (class "Default")
      (node (ref "R25") (pin "2") (pinfunction "2_2") (pintype "passive"))
      (node (ref "R26") (pin "2") (pinfunction "2_2") (pintype "passive"))
      (node (ref "VT5") (pin "B") (pinfunction "B_B") (pintype "passive"))
    )
    (net (code "71") (name "Net-(R34-Pad1)") (class "Default")
      (node (ref "R34") (pin "1") (pinfunction "1_1") (pintype "passive"))
      (node (ref "R37") (pin "1") (pinfunction "1_1") (pintype "passive"))
      (node (ref "SA5") (pin "SENSE") (pinfunction "SENSE_SENSE") (pintype "output"))
    )
    (net (code "72") (name "Net-(R35-Pad2)") (class "Default")
      (node (ref "R35") (pin "2") (pinfunction "2_2") (pintype "passive"))
      (node (ref "R36") (pin "2") (pinfunction "2_2") (pintype "passive"))
      (node (ref "VT6") (pin "B") (pinfunction "B_B") (pintype "passive"))
    )
    (net (code "73") (name "Net-(SA5-PadGND)") (class "Default")
      (node (ref "SA5") (pin "GND") (pinfunction "GND_GND") (pintype "power_in"))
      (node (ref "VD7") (pin "A") (pinfunction "A_A") (pintype "passive"))
      (node (ref "VT6") (pin "C") (pinfunction "C_C") (pintype "passive"))
    )
    (net (code "74") (name "Net-(TR1-PadW1-1)") (class "Default")
      (node (ref "TR1") (pin "W1-1") (pinfunction "W1-1_W1-1") (pintype "bidirectional"))
      (node (ref "VD2") (pin "C") (pinfunction "C_C") (pintype "passive"))
      (node (ref "VT5") (pin "C") (pinfunction "C_C") (pintype "passive"))
    )
    (net (code "75") (name "Net-(TR1-PadW1-2)") (class "Default")
      (node (ref "TR1") (pin "W1-2") (pinfunction "W1-2_W1-2") (pintype "bidirectional"))
      (node (ref "VD1") (pin "C") (pinfunction "C_C") (pintype "passive"))
      (node (ref "VT4") (pin "C") (pinfunction "C_C") (pintype "passive"))
    )
    (net (code "76") (name "Net-(TR1-PadW2-1)") (class "Default")
      (node (ref "TR1") (pin "W2-1") (pinfunction "W2-1_W2-1") (pintype "bidirectional"))
      (node (ref "VD3") (pin "A") (pinfunction "A_A") (pintype "passive"))
    )
    (net (code "77") (name "Net-(TR1-PadW2-2)") (class "Default")
      (node (ref "TR1") (pin "W2-2") (pinfunction "W2-2_W2-2") (pintype "bidirectional"))
      (node (ref "VD4") (pin "A") (pinfunction "A_A") (pintype "passive"))
    )
    (net (code "78") (name "Net-(TR1-PadW3-1)") (class "Default")
      (node (ref "TR1") (pin "W3-1") (pinfunction "W3-1_W3-1") (pintype "bidirectional"))
      (node (ref "VD5") (pin "A") (pinfunction "A_A") (pintype "passive"))
    )
    (net (code "79") (name "Net-(TR1-PadW3-2)") (class "Default")
      (node (ref "TR1") (pin "W3-2") (pinfunction "W3-2_W3-2") (pintype "bidirectional"))
      (node (ref "VD6") (pin "A") (pinfunction "A_A") (pintype "passive"))
    )
    (net (code "80") (name "Net-(VT3-G)") (class "Default")
      (node (ref "C18") (pin "1") (pinfunction "1_1") (pintype "passive"))
      (node (ref "R20") (pin "2") (pinfunction "2_2") (pintype "passive"))
      (node (ref "R21") (pin "1") (pinfunction "1_1") (pintype "passive"))
      (node (ref "VT3") (pin "1") (pinfunction "G_1") (pintype "passive"))
    )
    (net (code "81") (name "unconnected-(DD2-CTS-Pad11)") (class "Default")
      (node (ref "DD2") (pin "11") (pinfunction "CTS_11") (pintype "input"))
    )
    (net (code "82") (name "unconnected-(DD2-DCD-Pad10)") (class "Default")
      (node (ref "DD2") (pin "10") (pinfunction "DCD_10") (pintype "input"))
    )
    (net (code "83") (name "unconnected-(DD2-DSR-Pad9)") (class "Default")
      (node (ref "DD2") (pin "9") (pinfunction "DSR_9") (pintype "input"))
    )
    (net (code "84") (name "unconnected-(DD2-DTR-Pad2)") (class "Default")
      (node (ref "DD2") (pin "2") (pinfunction "DTR_2") (pintype "output"))
    )
    (net (code "85") (name "unconnected-(DD2-OSCI-Pad27)") (class "Default")
      (node (ref "DD2") (pin "27") (pinfunction "OSCI_27") (pintype "input"))
    )
    (net (code "86") (name "unconnected-(DD2-OSCO-Pad28)") (class "Default")
      (node (ref "DD2") (pin "28") (pinfunction "OSCO_28") (pintype "output"))
    )
    (net (code "87") (name "unconnected-(DD2-RESET-Pad19)") (class "Default")
      (node (ref "DD2") (pin "19") (pinfunction "RESET_19") (pintype "input"))
    )
    (net (code "88") (name "unconnected-(DD2-RI-Pad6)") (class "Default")
      (node (ref "DD2") (pin "6") (pinfunction "RI_6") (pintype "input"))
    )
    (net (code "89") (name "unconnected-(DD2-RTS-Pad3)") (class "Default")
      (node (ref "DD2") (pin "3") (pinfunction "RTS_3") (pintype "output"))
    )
    (net (code "90") (name "unconnected-(DD2-RXLED-Pad22)") (class "Default")
      (node (ref "DD2") (pin "22") (pinfunction "RXLED_22") (pintype "input"))
    )
    (net (code "91") (name "unconnected-(DD2-SLEEP-Pad12)") (class "Default")
      (node (ref "DD2") (pin "12") (pinfunction "SLEEP_12") (pintype "input"))
    )
    (net (code "92") (name "unconnected-(DD2-TXDEN-Pad13)") (class "Default")
      (node (ref "DD2") (pin "13") (pinfunction "TXDEN_13") (pintype "input"))
    )
    (net (code "93") (name "unconnected-(DD2-TXLED-Pad23)") (class "Default")
      (node (ref "DD2") (pin "23") (pinfunction "TXLED_23") (pintype "input"))
    )
    (net (code "94") (name "unconnected-(DD3-GP3-Pad6)") (class "Default")
      (node (ref "DD3") (pin "6") (pinfunction "GP3_6") (pintype "input"))
    )
    (net (code "95") (name "unconnected-(GLCD1-PadNC1)") (class "Default")
      (node (ref "GLCD1") (pin "NC1") (pinfunction "NC1_NC1") (pintype "no_connect"))
    )
    (net (code "96") (name "unconnected-(GLCD1-PadNC2)") (class "Default")
      (node (ref "GLCD1") (pin "NC2") (pinfunction "NC2_NC2") (pintype "no_connect"))
    )
    (net (code "97") (name "unconnected-(GLCD1-PadNC3)") (class "Default")
      (node (ref "GLCD1") (pin "NC3") (pinfunction "NC3_NC3") (pintype "no_connect"))
    )
    (net (code "98") (name "unconnected-(GLCD1-PadNC4)") (class "Default")
      (node (ref "GLCD1") (pin "NC4") (pinfunction "NC4_NC4") (pintype "no_connect"))
    )
    (net (code "99") (name "unconnected-(GLCD1-PadNC5)") (class "Default")
      (node (ref "GLCD1") (pin "NC5") (pinfunction "NC5_NC5") (pintype "no_connect"))
    )
    (net (code "100") (name "unconnected-(GLCD1-PadNC6)") (class "Default")
      (node (ref "GLCD1") (pin "NC6") (pinfunction "NC6_NC6") (pintype "no_connect"))
    )
    (net (code "101") (name "unconnected-(GLCD1-PadNC7)") (class "Default")
      (node (ref "GLCD1") (pin "NC7") (pinfunction "NC7_NC7") (pintype "no_connect"))
    )
    (net (code "102") (name "unconnected-(GLCD1-PadNC8)") (class "Default")
      (node (ref "GLCD1") (pin "NC8") (pinfunction "NC8_NC8") (pintype "no_connect"))
    )
    (net (code "103") (name "unconnected-(LED1-PadNC1)") (class "Default")
      (node (ref "LED1") (pin "NC1") (pinfunction "NC1_NC1") (pintype "no_connect"))
    )
    (net (code "104") (name "unconnected-(LED1-PadNC2)") (class "Default")
      (node (ref "LED1") (pin "NC2") (pinfunction "NC2_NC2") (pintype "no_connect"))
    )
    (net (code "105") (name "unconnected-(U$1-MTN1-PadMTN3)") (class "Default")
      (node (ref "U$1") (pin "MTN3") (pinfunction "MTN1_MTN3") (pintype "bidirectional"))
    )
    (net (code "106") (name "unconnected-(U$1-MTN2-PadMTN1)") (class "Default")
      (node (ref "U$1") (pin "MTN1") (pinfunction "MTN2_MTN1") (pintype "bidirectional"))
    )
    (net (code "107") (name "unconnected-(U$1-MTN3-PadMTN2)") (class "Default")
      (node (ref "U$1") (pin "MTN2") (pinfunction "MTN3_MTN2") (pintype "bidirectional"))
    )
    (net (code "108") (name "unconnected-(U$1-PadID)") (class "Default")
      (node (ref "U$1") (pin "ID") (pinfunction "ID_ID") (pintype "bidirectional"))
    )
    (net (code "109") (name "unconnected-(U$1-PadMTN4)") (class "Default")
      (node (ref "U$1") (pin "MTN4") (pinfunction "MTN4_MTN4") (pintype "bidirectional"))
    )
  )
)
